# Charger_2023_itr1_ver8.net
KiCad netlist of a schematic drawn in EAGLE
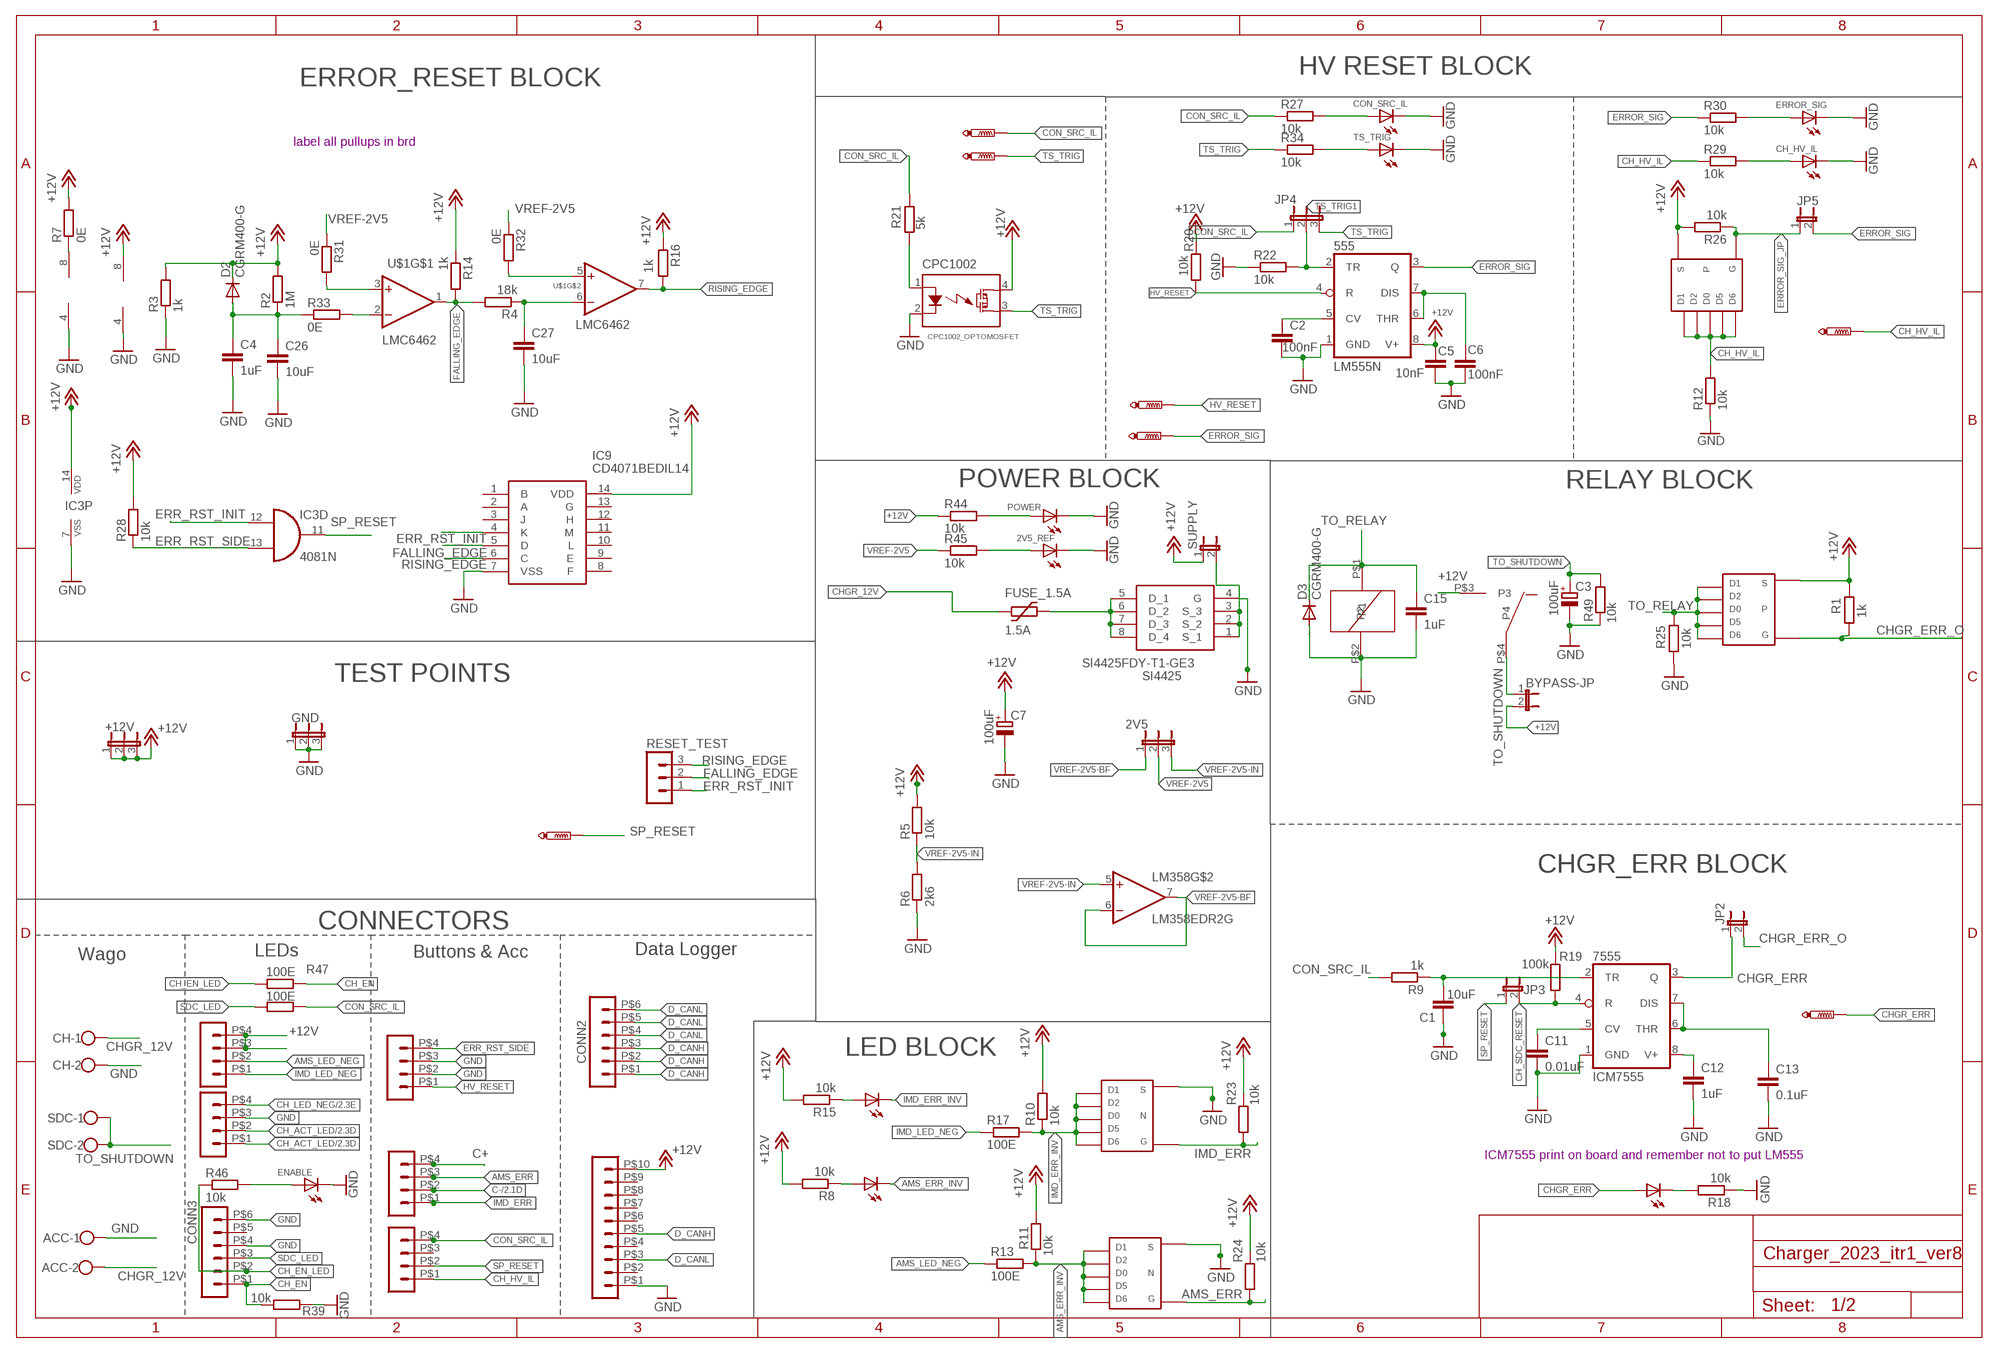
[diagram p0: schematic, sheet 1]
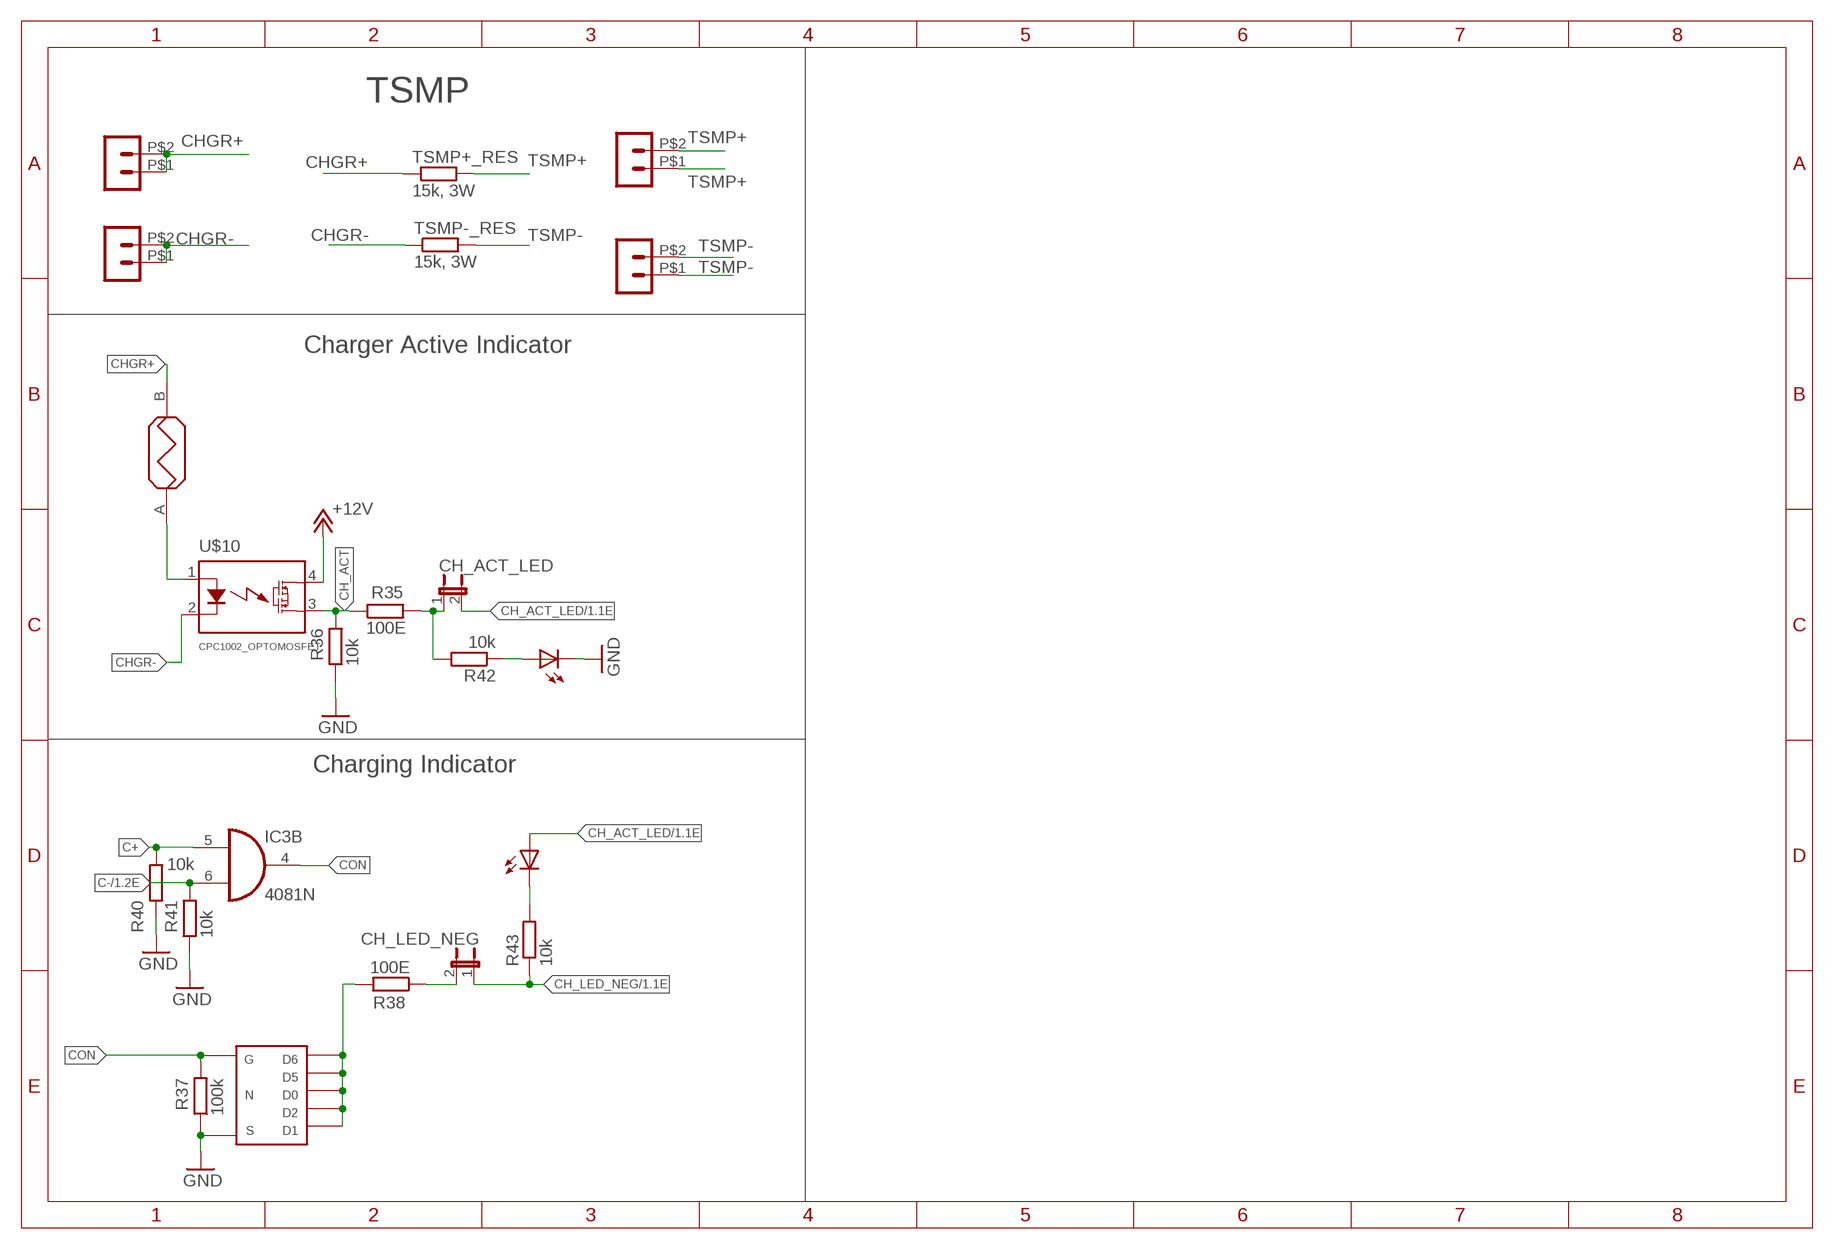
[diagram p1: schematic, sheet 2]

(export (version "E")
  (design (tool "Eeschema 10.0.6"))
  (components
    (comp (ref "+12V")
      (value "JP2E")
      (footprint "eagle-import:JP2")
      (libsource (lib "eagle-import") (part "JP2E"))
    )
    (comp (ref "2V5")
      (value "JP2E")
      (footprint "eagle-import:JP2")
      (libsource (lib "eagle-import") (part "JP2E"))
    )
    (comp (ref "2V5_REF")
      (value "LED-FKIT-1206")
      (footprint "eagle-import:FKIT-LED-1206")
      (libsource (lib "eagle-import") (part "LED-FKIT-1206"))
    )
    (comp (ref "555")
      (value "LM555N")
      (footprint "eagle-import:DIL08")
      (libsource (lib "eagle-import") (part "555NLM"))
    )
    (comp (ref "7555")
      (value "ICM7555")
      (footprint "eagle-import:DIL08")
      (libsource (lib "eagle-import") (part "555NLM"))
    )
    (comp (ref "ACC")
      (value "W237-102")
      (footprint "eagle-import:W237-102")
      (fields (field (name "MPN") "237-102"))
      (libsource (lib "eagle-import") (part "W237-102"))
    )
    (comp (ref "ACU")
      (value "HEADER_POS4_43045-0412")
      (footprint "eagle-import:43045-0412")
      (libsource (lib "eagle-import") (part "HEADER_POS4_?43045-0412"))
    )
    (comp (ref "ACU1")
      (value "HEADER_POS4_43045-0412")
      (footprint "eagle-import:43045-0412")
      (libsource (lib "eagle-import") (part "HEADER_POS4_?43045-0412"))
    )
    (comp (ref "ACU2")
      (value "HEADER_POS4_43045-0412")
      (footprint "eagle-import:43045-0412")
      (libsource (lib "eagle-import") (part "HEADER_POS4_?43045-0412"))
    )
    (comp (ref "ACU3")
      (value "HEADER_POS4_43045-0412")
      (footprint "eagle-import:43045-0412")
      (libsource (lib "eagle-import") (part "HEADER_POS4_?43045-0412"))
    )
    (comp (ref "ACU4")
      (value "HEADER_POS4_43045-0412")
      (footprint "eagle-import:43045-0412")
      (libsource (lib "eagle-import") (part "HEADER_POS4_?43045-0412"))
    )
    (comp (ref "AMS")
      (value "LED-FKIT-1206")
      (footprint "eagle-import:FKIT-LED-1206")
      (libsource (lib "eagle-import") (part "LED-FKIT-1206"))
    )
    (comp (ref "BYPASS-JP")
      (value "JP1E")
      (footprint "eagle-import:JP1")
      (libsource (lib "eagle-import") (part "JP1E"))
    )
    (comp (ref "C1")
      (value "10uF")
      (footprint "eagle-import:C0805")
      (libsource (lib "eagle-import") (part "C-EUC0805"))
    )
    (comp (ref "C2")
      (value "100nF")
      (footprint "eagle-import:C0805")
      (libsource (lib "eagle-import") (part "C-EUC0805"))
    )
    (comp (ref "C3")
      (value "100uF")
      (footprint "eagle-import:E2,5-6")
      (libsource (lib "eagle-import") (part "CPOL-EUE2.5-6"))
    )
    (comp (ref "C4")
      (value "1uF")
      (footprint "eagle-import:C0805")
      (libsource (lib "eagle-import") (part "C-EUC0805"))
    )
    (comp (ref "C5")
      (value "10nF")
      (footprint "eagle-import:C0805")
      (libsource (lib "eagle-import") (part "C-EUC0805"))
    )
    (comp (ref "C6")
      (value "100nF")
      (footprint "eagle-import:C0805")
      (libsource (lib "eagle-import") (part "C-EUC0805"))
    )
    (comp (ref "C7")
      (value "100uF")
      (footprint "eagle-import:E2,5-6")
      (libsource (lib "eagle-import") (part "CPOL-EUE2.5-6"))
    )
    (comp (ref "C11")
      (value "0.01uF")
      (footprint "eagle-import:C0805")
      (libsource (lib "eagle-import") (part "C-EUC0805"))
    )
    (comp (ref "C12")
      (value "1uF")
      (footprint "eagle-import:C0805")
      (libsource (lib "eagle-import") (part "C-EUC0805"))
    )
    (comp (ref "C13")
      (value "0.1uF")
      (footprint "eagle-import:C0805")
      (libsource (lib "eagle-import") (part "C-EUC0805"))
    )
    (comp (ref "C15")
      (value "1uF")
      (footprint "eagle-import:C0805")
      (libsource (lib "eagle-import") (part "C-EUC0805"))
    )
    (comp (ref "C26")
      (value "10uF")
      (footprint "eagle-import:C0805")
      (libsource (lib "eagle-import") (part "C-EUC0805"))
    )
    (comp (ref "C27")
      (value "10uF")
      (footprint "eagle-import:C0805")
      (libsource (lib "eagle-import") (part "C-EUC0805"))
    )
    (comp (ref "CH")
      (value "W237-102")
      (footprint "eagle-import:W237-102")
      (fields (field (name "MPN") "237-102"))
      (libsource (lib "eagle-import") (part "W237-102"))
    )
    (comp (ref "CH-HV-IL")
      (value "PTR1PAD1-13")
      (footprint "eagle-import:P1-13")
      (libsource (lib "eagle-import") (part "PTR1PAD1-13"))
    )
    (comp (ref "CHGR-ERR")
      (value "PTR1PAD1-13")
      (footprint "eagle-import:P1-13")
      (libsource (lib "eagle-import") (part "PTR1PAD1-13"))
    )
    (comp (ref "CHGR_ERR")
      (value "LED-FKIT-1206")
      (footprint "eagle-import:FKIT-LED-1206")
      (libsource (lib "eagle-import") (part "LED-FKIT-1206"))
    )
    (comp (ref "CH_HV_IL")
      (value "LED-FKIT-1206")
      (footprint "eagle-import:FKIT-LED-1206")
      (libsource (lib "eagle-import") (part "LED-FKIT-1206"))
    )
    (comp (ref "CON-SRC-IL")
      (value "PTR1PAD1-13")
      (footprint "eagle-import:P1-13")
      (libsource (lib "eagle-import") (part "PTR1PAD1-13"))
    )
    (comp (ref "CONN2")
      (value "HEADER_POS6_43045-0612")
      (footprint "eagle-import:43045-0612")
      (libsource (lib "eagle-import") (part "HEADER_POS6_?43045-0612"))
    )
    (comp (ref "CONN3")
      (value "HEADER_POS6_43045-0612")
      (footprint "eagle-import:43045-0612")
      (libsource (lib "eagle-import") (part "HEADER_POS6_?43045-0612"))
    )
    (comp (ref "CON_SRC_IL")
      (value "LED-FKIT-1206")
      (footprint "eagle-import:FKIT-LED-1206")
      (libsource (lib "eagle-import") (part "LED-FKIT-1206"))
    )
    (comp (ref "CPC1002")
      (value "CPC1002_OPTOMOSFET")
      (footprint "eagle-import:SOP04")
      (libsource (lib "eagle-import") (part "CPC1002_OPTOMOSFET"))
    )
    (comp (ref "D2")
      (value "CGRM400-G")
      (footprint "eagle-import:SOD-123_MINI-SMA")
      (libsource (lib "eagle-import") (part "CGRM400-G"))
    )
    (comp (ref "D3")
      (value "CGRM400-G")
      (footprint "eagle-import:SOD-123_MINI-SMA")
      (libsource (lib "eagle-import") (part "CGRM400-G"))
    )
    (comp (ref "ENABLE")
      (value "LED-FKIT-1206")
      (footprint "eagle-import:FKIT-LED-1206")
      (libsource (lib "eagle-import") (part "LED-FKIT-1206"))
    )
    (comp (ref "ERROR-SIG")
      (value "PTR1PAD1-13")
      (footprint "eagle-import:P1-13")
      (libsource (lib "eagle-import") (part "PTR1PAD1-13"))
    )
    (comp (ref "ERROR_SIG")
      (value "LED-FKIT-1206")
      (footprint "eagle-import:FKIT-LED-1206")
      (libsource (lib "eagle-import") (part "LED-FKIT-1206"))
    )
    (comp (ref "FUSE_1.5A")
      (value "1.5A")
      (footprint "eagle-import:1206L")
      (fields (field (name "MFR") "Littelfuse"))
      (libsource (lib "eagle-import") (part "1206L"))
    )
    (comp (ref "GND")
      (value "JP2E")
      (footprint "eagle-import:JP2")
      (libsource (lib "eagle-import") (part "JP2E"))
    )
    (comp (ref "HV-RESET")
      (value "PTR1PAD1-13")
      (footprint "eagle-import:P1-13")
      (libsource (lib "eagle-import") (part "PTR1PAD1-13"))
    )
    (comp (ref "IC3")
      (value "4081N")
      (footprint "eagle-import:DIL14")
      (libsource (lib "eagle-import") (part "4081N"))
    )
    (comp (ref "IC9")
      (value "CD4071BEDIL14")
      (footprint "eagle-import:DIL14")
      (libsource (lib "eagle-import") (part "CD4071BEDIL14"))
    )
    (comp (ref "IMD")
      (value "LED-FKIT-1206")
      (footprint "eagle-import:FKIT-LED-1206")
      (libsource (lib "eagle-import") (part "LED-FKIT-1206"))
    )
    (comp (ref "JP2")
      (value "JP1E")
      (footprint "eagle-import:JP1")
      (libsource (lib "eagle-import") (part "JP1E"))
    )
    (comp (ref "JP3")
      (value "JP1E")
      (footprint "eagle-import:JP1")
      (libsource (lib "eagle-import") (part "JP1E"))
    )
    (comp (ref "JP4")
      (value "JP2E")
      (footprint "eagle-import:JP2")
      (libsource (lib "eagle-import") (part "JP2E"))
    )
    (comp (ref "JP5")
      (value "JP1E")
      (footprint "eagle-import:JP1")
      (libsource (lib "eagle-import") (part "JP1E"))
    )
    (comp (ref "LM358")
      (value "LM358EDR2G")
      (footprint "eagle-import:SOIC-8")
      (libsource (lib "eagle-import") (part "LM358EDR2G"))
    )
    (comp (ref "POWER")
      (value "LED-FKIT-1206")
      (footprint "eagle-import:FKIT-LED-1206")
      (libsource (lib "eagle-import") (part "LED-FKIT-1206"))
    )
    (comp (ref "R1")
      (value "1k")
      (footprint "eagle-import:R0805")
      (libsource (lib "eagle-import") (part "R-EU_R0805"))
    )
    (comp (ref "R2")
      (value "1M")
      (footprint "eagle-import:R0805")
      (libsource (lib "eagle-import") (part "R-EU_R0805"))
    )
    (comp (ref "R3")
      (value "1k")
      (footprint "eagle-import:R0805")
      (libsource (lib "eagle-import") (part "R-EU_R0805"))
    )
    (comp (ref "R4")
      (value "18k")
      (footprint "eagle-import:R0805")
      (libsource (lib "eagle-import") (part "R-EU_R0805"))
    )
    (comp (ref "R5")
      (value "10k")
      (footprint "eagle-import:R0805")
      (libsource (lib "eagle-import") (part "R-EU_R0805"))
    )
    (comp (ref "R6")
      (value "2k6")
      (footprint "eagle-import:R0805")
      (libsource (lib "eagle-import") (part "R-EU_R0805"))
    )
    (comp (ref "R7")
      (value "0E")
      (footprint "eagle-import:R0805")
      (libsource (lib "eagle-import") (part "R-EU_R0805"))
    )
    (comp (ref "R8")
      (value "10k")
      (footprint "eagle-import:R0805")
      (libsource (lib "eagle-import") (part "R-EU_R0805"))
    )
    (comp (ref "R9")
      (value "1k")
      (footprint "eagle-import:R0805")
      (libsource (lib "eagle-import") (part "R-EU_R0805"))
    )
    (comp (ref "R10")
      (value "10k")
      (footprint "eagle-import:R0805")
      (libsource (lib "eagle-import") (part "R-EU_R0805"))
    )
    (comp (ref "R11")
      (value "10k")
      (footprint "eagle-import:R0805")
      (libsource (lib "eagle-import") (part "R-EU_R0805"))
    )
    (comp (ref "R12")
      (value "10k")
      (footprint "eagle-import:R0805")
      (libsource (lib "eagle-import") (part "R-EU_R0805"))
    )
    (comp (ref "R13")
      (value "100E")
      (footprint "eagle-import:M0805")
      (libsource (lib "eagle-import") (part "rcl_334_R-EU_M0805"))
    )
    (comp (ref "R14")
      (value "1k")
      (footprint "eagle-import:R0805")
      (libsource (lib "eagle-import") (part "R-EU_R0805"))
    )
    (comp (ref "R15")
      (value "10k")
      (footprint "eagle-import:R0805")
      (libsource (lib "eagle-import") (part "R-EU_R0805"))
    )
    (comp (ref "R16")
      (value "1k")
      (footprint "eagle-import:R0805")
      (libsource (lib "eagle-import") (part "R-EU_R0805"))
    )
    (comp (ref "R17")
      (value "100E")
      (footprint "eagle-import:M0805")
      (libsource (lib "eagle-import") (part "rcl_334_R-EU_M0805"))
    )
    (comp (ref "R18")
      (value "10k")
      (footprint "eagle-import:R0805")
      (libsource (lib "eagle-import") (part "R-EU_R0805"))
    )
    (comp (ref "R19")
      (value "100k")
      (footprint "eagle-import:R0805")
      (libsource (lib "eagle-import") (part "R-EU_R0805"))
    )
    (comp (ref "R20")
      (value "10k")
      (footprint "eagle-import:R0805")
      (libsource (lib "eagle-import") (part "R-EU_R0805"))
    )
    (comp (ref "R21")
      (value "5k")
      (footprint "eagle-import:R0805")
      (libsource (lib "eagle-import") (part "R-EU_R0805"))
    )
    (comp (ref "R22")
      (value "10k")
      (footprint "eagle-import:R0805")
      (libsource (lib "eagle-import") (part "R-EU_R0805"))
    )
    (comp (ref "R23")
      (value "10k")
      (footprint "eagle-import:R0805")
      (libsource (lib "eagle-import") (part "R-EU_R0805"))
    )
    (comp (ref "R24")
      (value "10k")
      (footprint "eagle-import:R0805")
      (libsource (lib "eagle-import") (part "R-EU_R0805"))
    )
    (comp (ref "R25")
      (value "10k")
      (footprint "eagle-import:R0805")
      (libsource (lib "eagle-import") (part "R-EU_R0805"))
    )
    (comp (ref "R26")
      (value "10k")
      (footprint "eagle-import:R0805")
      (libsource (lib "eagle-import") (part "R-EU_R0805"))
    )
    (comp (ref "R27")
      (value "10k")
      (footprint "eagle-import:R0805")
      (libsource (lib "eagle-import") (part "R-EU_R0805"))
    )
    (comp (ref "R28")
      (value "10k")
      (footprint "eagle-import:R0805")
      (libsource (lib "eagle-import") (part "R-EU_R0805"))
    )
    (comp (ref "R29")
      (value "10k")
      (footprint "eagle-import:R0805")
      (libsource (lib "eagle-import") (part "R-EU_R0805"))
    )
    (comp (ref "R30")
      (value "10k")
      (footprint "eagle-import:R0805")
      (libsource (lib "eagle-import") (part "R-EU_R0805"))
    )
    (comp (ref "R31")
      (value "0E")
      (footprint "eagle-import:R0805")
      (libsource (lib "eagle-import") (part "R-EU_R0805"))
    )
    (comp (ref "R32")
      (value "0E")
      (footprint "eagle-import:R0805")
      (libsource (lib "eagle-import") (part "R-EU_R0805"))
    )
    (comp (ref "R33")
      (value "0E")
      (footprint "eagle-import:R0805")
      (libsource (lib "eagle-import") (part "R-EU_R0805"))
    )
    (comp (ref "R34")
      (value "10k")
      (footprint "eagle-import:R0805")
      (libsource (lib "eagle-import") (part "R-EU_R0805"))
    )
    (comp (ref "R39")
      (value "10k")
      (footprint "eagle-import:R0805")
      (libsource (lib "eagle-import") (part "R-EU_R0805"))
    )
    (comp (ref "R44")
      (value "10k")
      (footprint "eagle-import:R0805")
      (libsource (lib "eagle-import") (part "R-EU_R0805"))
    )
    (comp (ref "R45")
      (value "10k")
      (footprint "eagle-import:R0805")
      (libsource (lib "eagle-import") (part "R-EU_R0805"))
    )
    (comp (ref "R46")
      (value "10k")
      (footprint "eagle-import:R0805")
      (libsource (lib "eagle-import") (part "R-EU_R0805"))
    )
    (comp (ref "R47")
      (value "100E")
      (footprint "eagle-import:R0805")
      (libsource (lib "eagle-import") (part "R-EU_R0805"))
    )
    (comp (ref "R48")
      (value "100E")
      (footprint "eagle-import:R0805")
      (libsource (lib "eagle-import") (part "R-EU_R0805"))
    )
    (comp (ref "R49")
      (value "10k")
      (footprint "eagle-import:R0805")
      (libsource (lib "eagle-import") (part "R-EU_R0805"))
    )
    (comp (ref "RESET_TEST")
      (value "MA03-1")
      (footprint "eagle-import:MA03-1")
      (libsource (lib "eagle-import") (part "MA03-1"))
    )
    (comp (ref "SDC")
      (value "W237-102")
      (footprint "eagle-import:W237-102")
      (fields (field (name "MPN") "237-102"))
      (libsource (lib "eagle-import") (part "W237-102"))
    )
    (comp (ref "SI4425")
      (value "SI4425FDY-T1-GE3")
      (footprint "eagle-import:SOIC127P600X175-8N")
      (fields (field (name "MOUSER_PART_NUMBER") "78-SI4425FDY-T1-GE3"))
      (libsource (lib "eagle-import") (part "SI4425FDY-T1-GE3"))
    )
    (comp (ref "SP_RESET")
      (value "PTR1PAD1-13")
      (footprint "eagle-import:P1-13")
      (libsource (lib "eagle-import") (part "PTR1PAD1-13"))
    )
    (comp (ref "SUPPLY")
      (value "JP1E")
      (footprint "eagle-import:JP1")
      (libsource (lib "eagle-import") (part "JP1E"))
    )
    (comp (ref "TS-TRIG")
      (value "PTR1PAD1-13")
      (footprint "eagle-import:P1-13")
      (libsource (lib "eagle-import") (part "PTR1PAD1-13"))
    )
    (comp (ref "TS_TRIG")
      (value "LED-FKIT-1206")
      (footprint "eagle-import:FKIT-LED-1206")
      (libsource (lib "eagle-import") (part "LED-FKIT-1206"))
    )
    (comp (ref "U$1")
      (value "LMC6462")
      (footprint "eagle-import:S08")
      (libsource (lib "eagle-import") (part "LMC6462"))
    )
    (comp (ref "U$3")
      (value "TSOP-6_PMOS")
      (footprint "eagle-import:TSOP-6_PMOS")
      (libsource (lib "eagle-import") (part "TSOP-6_MOS_TSOP-6_PMOS"))
    )
    (comp (ref "U$5")
      (value "TSOP-6_NMOS")
      (footprint "eagle-import:TSOP-6_NMOS")
      (libsource (lib "eagle-import") (part "TSOP-6_NMOS"))
    )
    (comp (ref "U$7")
      (value "TSOP-6_NMOS")
      (footprint "eagle-import:TSOP-6_NMOS")
      (libsource (lib "eagle-import") (part "TSOP-6_NMOS"))
    )
    (comp (ref "U$8")
      (value "TSOP-6_PMOS")
      (footprint "eagle-import:TSOP-6_PMOS")
      (libsource (lib "eagle-import") (part "TSOP-6_PMOS"))
    )
    (comp (ref "U$9")
      (value "G6DN_RELAY")
      (footprint "eagle-import:G6DN_RELAY")
      (libsource (lib "eagle-import") (part "G6DN_RELAY"))
    )
    (comp (ref "X5")
      (value "HEADER_POS10_43045-1012")
      (footprint "eagle-import:43045-1012")
      (libsource (lib "eagle-import") (part "HEADER_POS10_?43045-1012"))
    )
    (comp (ref "CHARGING")
      (value "LED-FKIT-1206")
      (footprint "eagle-import:FKIT-LED-1206")
      (libsource (lib "eagle-import") (part "LED-FKIT-1206"))
    )
    (comp (ref "CH_ACT")
      (value "LED-FKIT-1206")
      (footprint "eagle-import:FKIT-LED-1206")
      (libsource (lib "eagle-import") (part "LED-FKIT-1206"))
    )
    (comp (ref "CH_ACT_LED")
      (value "JP1E")
      (footprint "eagle-import:JP1")
      (libsource (lib "eagle-import") (part "JP1E"))
    )
    (comp (ref "CH_LED_NEG")
      (value "JP1E")
      (footprint "eagle-import:JP1")
      (libsource (lib "eagle-import") (part "JP1E"))
    )
    (comp (ref "LV_ECU")
      (value "HEADER_POS2_43045-0212")
      (footprint "eagle-import:43045-0212")
      (libsource (lib "eagle-import") (part "HEADER_POS2_?43045-0212"))
    )
    (comp (ref "LV_ECU1")
      (value "HEADER_POS2_43045-0212")
      (footprint "eagle-import:43045-0212")
      (libsource (lib "eagle-import") (part "HEADER_POS2_?43045-0212"))
    )
    (comp (ref "LV_ECU2")
      (value "HEADER_POS2_43045-0212")
      (footprint "eagle-import:43045-0212")
      (libsource (lib "eagle-import") (part "HEADER_POS2_?43045-0212"))
    )
    (comp (ref "LV_ECU3")
      (value "HEADER_POS2_43045-0212")
      (footprint "eagle-import:43045-0212")
      (libsource (lib "eagle-import") (part "HEADER_POS2_?43045-0212"))
    )
    (comp (ref "R35")
      (value "100E")
      (footprint "eagle-import:M0805")
      (libsource (lib "eagle-import") (part "rcl_334_R-EU_M0805"))
    )
    (comp (ref "R36")
      (value "10k")
      (footprint "eagle-import:M0805")
      (libsource (lib "eagle-import") (part "rcl_334_R-EU_M0805"))
    )
    (comp (ref "R37")
      (value "100k")
      (footprint "eagle-import:M0805")
      (libsource (lib "eagle-import") (part "rcl_334_R-EU_M0805"))
    )
    (comp (ref "R38")
      (value "100E")
      (footprint "eagle-import:M0805")
      (libsource (lib "eagle-import") (part "rcl_334_R-EU_M0805"))
    )
    (comp (ref "R40")
      (value "10k")
      (footprint "eagle-import:M0805")
      (libsource (lib "eagle-import") (part "rcl_334_R-EU_M0805"))
    )
    (comp (ref "R41")
      (value "10k")
      (footprint "eagle-import:M0805")
      (libsource (lib "eagle-import") (part "rcl_334_R-EU_M0805"))
    )
    (comp (ref "R42")
      (value "10k")
      (footprint "eagle-import:R0805")
      (libsource (lib "eagle-import") (part "R-EU_R0805"))
    )
    (comp (ref "R43")
      (value "10k")
      (footprint "eagle-import:R0805")
      (libsource (lib "eagle-import") (part "R-EU_R0805"))
    )
    (comp (ref "TSMP+_RES")
      (value "15k, 3W")
      (footprint "eagle-import:P0613_15")
      (libsource (lib "eagle-import") (part "rcl_334_R-EU_0613/15"))
    )
    (comp (ref "TSMP-_RES")
      (value "15k, 3W")
      (footprint "eagle-import:P0613_15")
      (libsource (lib "eagle-import") (part "rcl_334_R-EU_0613/15"))
    )
    (comp (ref "U$2_100K10W2")
      (value "POWER_RESISTOR")
      (footprint "eagle-import:POWER_RESISTOR")
      (libsource (lib "eagle-import") (part "POWER_RESISTOR"))
    )
    (comp (ref "U$10")
      (value "CPC1002_OPTOMOSFET")
      (footprint "eagle-import:SOP04")
      (libsource (lib "eagle-import") (part "CPC1002_OPTOMOSFET"))
    )
    (comp (ref "U$12")
      (value "TSOP-6_NMOS")
      (footprint "eagle-import:TSOP-6_NMOS")
      (libsource (lib "eagle-import") (part "TSOP-6_NMOS"))
    )
  )
  (nets
    (net (code "1") (name "+12V") (class "Default")
      (node (ref "+12V") (pin "1") (pinfunction "1_1") (pintype "passive"))
      (node (ref "+12V") (pin "2") (pinfunction "2_2") (pintype "passive"))
      (node (ref "+12V") (pin "3") (pinfunction "3_3") (pintype "passive"))
      (node (ref "555") (pin "8") (pinfunction "V+_8") (pintype "power_in"))
      (node (ref "7555") (pin "8") (pinfunction "V+_8") (pintype "power_in"))
      (node (ref "ACU") (pin "P$3") (pinfunction "3_P$3") (pintype "passive"))
      (node (ref "ACU") (pin "P$4") (pinfunction "4_P$4") (pintype "passive"))
      (node (ref "BYPASS-JP") (pin "2") (pinfunction "2_2") (pintype "passive"))
      (node (ref "C12") (pin "1") (pinfunction "1_1") (pintype "passive"))
      (node (ref "C5") (pin "1") (pinfunction "1_1") (pintype "passive"))
      (node (ref "C7") (pin "+") (pinfunction "+_+") (pintype "passive"))
      (node (ref "CPC1002") (pin "4") (pinfunction "4_4") (pintype "passive"))
      (node (ref "D2") (pin "C") (pinfunction "C_C") (pintype "passive"))
      (node (ref "IC3") (pin "14") (pinfunction "VDD_14") (pintype "power_in"))
      (node (ref "IC9") (pin "14") (pinfunction "VDD_14") (pintype "power_in"))
      (node (ref "LM358") (pin "8") (pinfunction "V+_8") (pintype "power_in"))
      (node (ref "R1") (pin "2") (pinfunction "2_2") (pintype "passive"))
      (node (ref "R10") (pin "2") (pinfunction "2_2") (pintype "passive"))
      (node (ref "R11") (pin "2") (pinfunction "2_2") (pintype "passive"))
      (node (ref "R14") (pin "1") (pinfunction "1_1") (pintype "passive"))
      (node (ref "R15") (pin "2") (pinfunction "2_2") (pintype "passive"))
      (node (ref "R16") (pin "1") (pinfunction "1_1") (pintype "passive"))
      (node (ref "R19") (pin "1") (pinfunction "1_1") (pintype "passive"))
      (node (ref "R2") (pin "2") (pinfunction "2_2") (pintype "passive"))
      (node (ref "R20") (pin "2") (pinfunction "2_2") (pintype "passive"))
      (node (ref "R23") (pin "2") (pinfunction "2_2") (pintype "passive"))
      (node (ref "R24") (pin "2") (pinfunction "2_2") (pintype "passive"))
      (node (ref "R26") (pin "2") (pinfunction "2_2") (pintype "passive"))
      (node (ref "R28") (pin "2") (pinfunction "2_2") (pintype "passive"))
      (node (ref "R3") (pin "2") (pinfunction "2_2") (pintype "passive"))
      (node (ref "R44") (pin "1") (pinfunction "1_1") (pintype "passive"))
      (node (ref "R5") (pin "2") (pinfunction "2_2") (pintype "passive"))
      (node (ref "R7") (pin "2") (pinfunction "2_2") (pintype "passive"))
      (node (ref "R8") (pin "2") (pinfunction "2_2") (pintype "passive"))
      (node (ref "SUPPLY") (pin "1") (pinfunction "1_1") (pintype "passive"))
      (node (ref "U$10") (pin "4") (pinfunction "4_4") (pintype "passive"))
      (node (ref "U$3") (pin "S") (pinfunction "S_S") (pintype "bidirectional"))
      (node (ref "U$8") (pin "S") (pinfunction "S_S") (pintype "bidirectional"))
      (node (ref "U$9") (pin "P$3") (pinfunction "P3_P$3") (pintype "bidirectional"))
      (node (ref "X5") (pin "P$10") (pinfunction "10_P$10") (pintype "passive"))
    )
    (net (code "2") (name "AMS_ERR") (class "Default")
      (node (ref "ACU3") (pin "P$3") (pinfunction "3_P$3") (pintype "passive"))
      (node (ref "R24") (pin "1") (pinfunction "1_1") (pintype "passive"))
      (node (ref "U$5") (pin "G") (pinfunction "G_G") (pintype "bidirectional"))
    )
    (net (code "3") (name "AMS_ERR_INV") (class "Default")
      (node (ref "AMS") (pin "C") (pinfunction "C_C") (pintype "passive"))
      (node (ref "R11") (pin "1") (pinfunction "1_1") (pintype "passive"))
      (node (ref "R13") (pin "2") (pinfunction "2_2") (pintype "passive"))
      (node (ref "U$5") (pin "1") (pinfunction "1_1") (pintype "bidirectional"))
      (node (ref "U$5") (pin "2") (pinfunction "2_2") (pintype "bidirectional"))
      (node (ref "U$5") (pin "5") (pinfunction "5_5") (pintype "bidirectional"))
      (node (ref "U$5") (pin "6") (pinfunction "6_6") (pintype "bidirectional"))
      (node (ref "U$5") (pin "D") (pinfunction "D0_D") (pintype "bidirectional"))
    )
    (net (code "4") (name "AMS_LED_NEG") (class "Default")
      (node (ref "ACU") (pin "P$2") (pinfunction "2_P$2") (pintype "passive"))
      (node (ref "R13") (pin "1") (pinfunction "1_1") (pintype "passive"))
    )
    (net (code "5") (name "C+") (class "Default")
      (node (ref "ACU3") (pin "P$4") (pinfunction "4_P$4") (pintype "passive"))
      (node (ref "IC3") (pin "5") (pinfunction "I0_5") (pintype "input"))
      (node (ref "R40") (pin "2") (pinfunction "2_2") (pintype "passive"))
    )
    (net (code "6") (name "C-") (class "Default")
      (node (ref "ACU3") (pin "P$2") (pinfunction "2_P$2") (pintype "passive"))
      (node (ref "IC3") (pin "6") (pinfunction "I1_6") (pintype "input"))
      (node (ref "R41") (pin "2") (pinfunction "2_2") (pintype "passive"))
    )
    (net (code "7") (name "CHGR+") (class "Default")
      (node (ref "LV_ECU2") (pin "P$1") (pinfunction "1_P$1") (pintype "passive"))
      (node (ref "LV_ECU2") (pin "P$2") (pinfunction "2_P$2") (pintype "passive"))
      (node (ref "TSMP+_RES") (pin "1") (pinfunction "1_1") (pintype "passive"))
      (node (ref "U$2_100K10W2") (pin "B") (pinfunction "B_B") (pintype "bidirectional"))
    )
    (net (code "8") (name "CHGR-") (class "Default")
      (node (ref "LV_ECU3") (pin "P$1") (pinfunction "1_P$1") (pintype "passive"))
      (node (ref "LV_ECU3") (pin "P$2") (pinfunction "2_P$2") (pintype "passive"))
      (node (ref "TSMP-_RES") (pin "1") (pinfunction "1_1") (pintype "passive"))
      (node (ref "U$10") (pin "2") (pinfunction "2_2") (pintype "passive"))
    )
    (net (code "9") (name "CHGR_12V") (class "Default")
      (node (ref "ACC") (pin "2") (pinfunction "KL_2") (pintype "passive"))
      (node (ref "CH") (pin "1") (pinfunction "KL_1") (pintype "passive"))
      (node (ref "FUSE_1.5A") (pin "P$1") (pinfunction "1_P$1") (pintype "passive"))
    )
    (net (code "10") (name "CHGR_ERR") (class "Default")
      (node (ref "7555") (pin "3") (pinfunction "Q_3") (pintype "output"))
      (node (ref "CHGR-ERR") (pin "TP") (pinfunction "TP_TP") (pintype "input"))
      (node (ref "CHGR_ERR") (pin "A") (pinfunction "A_A") (pintype "passive"))
      (node (ref "JP2") (pin "1") (pinfunction "1_1") (pintype "passive"))
    )
    (net (code "11") (name "CHGR_ERR_O") (class "Default")
      (node (ref "JP2") (pin "2") (pinfunction "2_2") (pintype "passive"))
      (node (ref "R1") (pin "1") (pinfunction "1_1") (pintype "passive"))
      (node (ref "U$3") (pin "G") (pinfunction "G_G") (pintype "bidirectional"))
    )
    (net (code "12") (name "CH_ACT") (class "Default")
      (node (ref "R35") (pin "1") (pinfunction "1_1") (pintype "passive"))
      (node (ref "R36") (pin "2") (pinfunction "2_2") (pintype "passive"))
      (node (ref "U$10") (pin "3") (pinfunction "3_3") (pintype "passive"))
    )
    (net (code "13") (name "CH_ACT_LED") (class "Default")
      (node (ref "ACU2") (pin "P$1") (pinfunction "1_P$1") (pintype "passive"))
      (node (ref "ACU2") (pin "P$2") (pinfunction "2_P$2") (pintype "passive"))
      (node (ref "CHARGING") (pin "A") (pinfunction "A_A") (pintype "passive"))
      (node (ref "CH_ACT_LED") (pin "2") (pinfunction "2_2") (pintype "passive"))
    )
    (net (code "14") (name "CH_EN") (class "Default")
      (node (ref "CONN3") (pin "P$1") (pinfunction "1_P$1") (pintype "passive"))
      (node (ref "R39") (pin "2") (pinfunction "2_2") (pintype "passive"))
      (node (ref "R47") (pin "2") (pinfunction "2_2") (pintype "passive"))
    )
    (net (code "15") (name "CH_EN_LED") (class "Default")
      (node (ref "CONN3") (pin "P$2") (pinfunction "2_P$2") (pintype "passive"))
      (node (ref "R46") (pin "1") (pinfunction "1_1") (pintype "passive"))
      (node (ref "R47") (pin "1") (pinfunction "1_1") (pintype "passive"))
    )
    (net (code "16") (name "CH_HV_IL") (class "Default")
      (node (ref "ACU4") (pin "P$1") (pinfunction "1_P$1") (pintype "passive"))
      (node (ref "CH-HV-IL") (pin "TP") (pinfunction "TP_TP") (pintype "input"))
      (node (ref "R12") (pin "2") (pinfunction "2_2") (pintype "passive"))
      (node (ref "R29") (pin "1") (pinfunction "1_1") (pintype "passive"))
      (node (ref "U$8") (pin "1") (pinfunction "1_1") (pintype "bidirectional"))
      (node (ref "U$8") (pin "2") (pinfunction "2_2") (pintype "bidirectional"))
      (node (ref "U$8") (pin "5") (pinfunction "5_5") (pintype "bidirectional"))
      (node (ref "U$8") (pin "6") (pinfunction "6_6") (pintype "bidirectional"))
      (node (ref "U$8") (pin "D") (pinfunction "D0_D") (pintype "bidirectional"))
    )
    (net (code "17") (name "CH_LED_NEG") (class "Default")
      (node (ref "ACU2") (pin "P$4") (pinfunction "4_P$4") (pintype "passive"))
      (node (ref "CH_LED_NEG") (pin "1") (pinfunction "1_1") (pintype "passive"))
      (node (ref "R43") (pin "1") (pinfunction "1_1") (pintype "passive"))
    )
    (net (code "18") (name "CH_SDC_RESET") (class "Default")
      (node (ref "7555") (pin "4") (pinfunction "R_4") (pintype "input"))
      (node (ref "JP3") (pin "2") (pinfunction "2_2") (pintype "passive"))
      (node (ref "R19") (pin "2") (pinfunction "2_2") (pintype "passive"))
    )
    (net (code "19") (name "CON") (class "Default")
      (node (ref "IC3") (pin "4") (pinfunction "O_4") (pintype "output"))
      (node (ref "R37") (pin "2") (pinfunction "2_2") (pintype "passive"))
      (node (ref "U$12") (pin "G") (pinfunction "G_G") (pintype "bidirectional"))
    )
    (net (code "20") (name "CON_SRC_IL") (class "Default")
      (node (ref "ACU4") (pin "P$4") (pinfunction "4_P$4") (pintype "passive"))
      (node (ref "CON-SRC-IL") (pin "TP") (pinfunction "TP_TP") (pintype "input"))
      (node (ref "JP4") (pin "1") (pinfunction "1_1") (pintype "passive"))
      (node (ref "R21") (pin "2") (pinfunction "2_2") (pintype "passive"))
      (node (ref "R27") (pin "1") (pinfunction "1_1") (pintype "passive"))
      (node (ref "R48") (pin "2") (pinfunction "2_2") (pintype "passive"))
      (node (ref "R9") (pin "2") (pinfunction "2_2") (pintype "passive"))
    )
    (net (code "21") (name "D_CANH") (class "Default")
      (node (ref "CONN2") (pin "P$1") (pinfunction "1_P$1") (pintype "passive"))
      (node (ref "CONN2") (pin "P$2") (pinfunction "2_P$2") (pintype "passive"))
      (node (ref "CONN2") (pin "P$3") (pinfunction "3_P$3") (pintype "passive"))
      (node (ref "X5") (pin "P$5") (pinfunction "5_P$5") (pintype "passive"))
    )
    (net (code "22") (name "D_CANL") (class "Default")
      (node (ref "CONN2") (pin "P$4") (pinfunction "4_P$4") (pintype "passive"))
      (node (ref "CONN2") (pin "P$5") (pinfunction "5_P$5") (pintype "passive"))
      (node (ref "CONN2") (pin "P$6") (pinfunction "6_P$6") (pintype "passive"))
      (node (ref "X5") (pin "P$3") (pinfunction "3_P$3") (pintype "passive"))
    )
    (net (code "23") (name "ERROR_SIG") (class "Default")
      (node (ref "555") (pin "3") (pinfunction "Q_3") (pintype "output"))
      (node (ref "ERROR-SIG") (pin "TP") (pinfunction "TP_TP") (pintype "input"))
      (node (ref "JP5") (pin "2") (pinfunction "2_2") (pintype "passive"))
      (node (ref "R30") (pin "1") (pinfunction "1_1") (pintype "passive"))
    )
    (net (code "24") (name "ERROR_SIG_JP") (class "Default")
      (node (ref "JP5") (pin "1") (pinfunction "1_1") (pintype "passive"))
      (node (ref "R26") (pin "1") (pinfunction "1_1") (pintype "passive"))
      (node (ref "U$8") (pin "G") (pinfunction "G_G") (pintype "bidirectional"))
    )
    (net (code "25") (name "ERR_RST_INIT") (class "Default")
      (node (ref "IC3") (pin "12") (pinfunction "I0_12") (pintype "input"))
      (node (ref "IC9") (pin "4") (pinfunction "K_4") (pintype "bidirectional"))
      (node (ref "RESET_TEST") (pin "1") (pinfunction "1_1") (pintype "passive"))
    )
    (net (code "26") (name "ERR_RST_SIDE") (class "Default")
      (node (ref "ACU1") (pin "P$4") (pinfunction "4_P$4") (pintype "passive"))
      (node (ref "IC3") (pin "13") (pinfunction "I1_13") (pintype "input"))
      (node (ref "R28") (pin "1") (pinfunction "1_1") (pintype "passive"))
    )
    (net (code "27") (name "FALLING_EDGE") (class "Default")
      (node (ref "IC9") (pin "5") (pinfunction "D_5") (pintype "bidirectional"))
      (node (ref "R14") (pin "2") (pinfunction "2_2") (pintype "passive"))
      (node (ref "R4") (pin "2") (pinfunction "2_2") (pintype "passive"))
      (node (ref "RESET_TEST") (pin "2") (pinfunction "2_2") (pintype "passive"))
      (node (ref "U$1") (pin "1") (pinfunction "OUT_1") (pintype "output"))
    )
    (net (code "28") (name "GND") (class "Default")
      (node (ref "2V5_REF") (pin "C") (pinfunction "C_C") (pintype "passive"))
      (node (ref "555") (pin "1") (pinfunction "GND_1") (pintype "power_in"))
      (node (ref "7555") (pin "1") (pinfunction "GND_1") (pintype "power_in"))
      (node (ref "ACC") (pin "1") (pinfunction "KL_1") (pintype "passive"))
      (node (ref "ACU1") (pin "P$2") (pinfunction "2_P$2") (pintype "passive"))
      (node (ref "ACU1") (pin "P$3") (pinfunction "3_P$3") (pintype "passive"))
      (node (ref "ACU2") (pin "P$3") (pinfunction "3_P$3") (pintype "passive"))
      (node (ref "C1") (pin "1") (pinfunction "1_1") (pintype "passive"))
      (node (ref "C11") (pin "2") (pinfunction "2_2") (pintype "passive"))
      (node (ref "C12") (pin "2") (pinfunction "2_2") (pintype "passive"))
      (node (ref "C13") (pin "2") (pinfunction "2_2") (pintype "passive"))
      (node (ref "C15") (pin "2") (pinfunction "2_2") (pintype "passive"))
      (node (ref "C2") (pin "2") (pinfunction "2_2") (pintype "passive"))
      (node (ref "C26") (pin "2") (pinfunction "2_2") (pintype "passive"))
      (node (ref "C27") (pin "2") (pinfunction "2_2") (pintype "passive"))
      (node (ref "C3") (pin "-") (pinfunction "-_-") (pintype "passive"))
      (node (ref "C4") (pin "2") (pinfunction "2_2") (pintype "passive"))
      (node (ref "C5") (pin "2") (pinfunction "2_2") (pintype "passive"))
      (node (ref "C6") (pin "2") (pinfunction "2_2") (pintype "passive"))
      (node (ref "C7") (pin "-") (pinfunction "-_-") (pintype "passive"))
      (node (ref "CH") (pin "2") (pinfunction "KL_2") (pintype "passive"))
      (node (ref "CH_ACT") (pin "C") (pinfunction "C_C") (pintype "passive"))
      (node (ref "CH_HV_IL") (pin "C") (pinfunction "C_C") (pintype "passive"))
      (node (ref "CONN3") (pin "P$4") (pinfunction "4_P$4") (pintype "passive"))
      (node (ref "CONN3") (pin "P$6") (pinfunction "6_P$6") (pintype "passive"))
      (node (ref "CON_SRC_IL") (pin "C") (pinfunction "C_C") (pintype "passive"))
      (node (ref "CPC1002") (pin "2") (pinfunction "2_2") (pintype "passive"))
      (node (ref "D3") (pin "A") (pinfunction "A_A") (pintype "passive"))
      (node (ref "ENABLE") (pin "C") (pinfunction "C_C") (pintype "passive"))
      (node (ref "ERROR_SIG") (pin "C") (pinfunction "C_C") (pintype "passive"))
      (node (ref "GND") (pin "1") (pinfunction "1_1") (pintype "passive"))
      (node (ref "GND") (pin "2") (pinfunction "2_2") (pintype "passive"))
      (node (ref "GND") (pin "3") (pinfunction "3_3") (pintype "passive"))
      (node (ref "IC3") (pin "7") (pinfunction "VSS_7") (pintype "power_in"))
      (node (ref "IC9") (pin "7") (pinfunction "VSS_7") (pintype "power_in"))
      (node (ref "LM358") (pin "4") (pinfunction "V-_4") (pintype "power_in"))
      (node (ref "POWER") (pin "C") (pinfunction "C_C") (pintype "passive"))
      (node (ref "R12") (pin "1") (pinfunction "1_1") (pintype "passive"))
      (node (ref "R18") (pin "1") (pinfunction "1_1") (pintype "passive"))
      (node (ref "R22") (pin "1") (pinfunction "1_1") (pintype "passive"))
      (node (ref "R25") (pin "1") (pinfunction "1_1") (pintype "passive"))
      (node (ref "R3") (pin "1") (pinfunction "1_1") (pintype "passive"))
      (node (ref "R36") (pin "1") (pinfunction "1_1") (pintype "passive"))
      (node (ref "R37") (pin "1") (pinfunction "1_1") (pintype "passive"))
      (node (ref "R39") (pin "1") (pinfunction "1_1") (pintype "passive"))
      (node (ref "R40") (pin "1") (pinfunction "1_1") (pintype "passive"))
      (node (ref "R41") (pin "1") (pinfunction "1_1") (pintype "passive"))
      (node (ref "R49") (pin "1") (pinfunction "1_1") (pintype "passive"))
      (node (ref "R6") (pin "1") (pinfunction "1_1") (pintype "passive"))
      (node (ref "SI4425") (pin "4") (pinfunction "G_4") (pintype "bidirectional"))
      (node (ref "TS_TRIG") (pin "C") (pinfunction "C_C") (pintype "passive"))
      (node (ref "U$1") (pin "4") (pinfunction "V-_4") (pintype "power_in"))
      (node (ref "U$12") (pin "S") (pinfunction "S_S") (pintype "bidirectional"))
      (node (ref "U$5") (pin "S") (pinfunction "S_S") (pintype "bidirectional"))
      (node (ref "U$7") (pin "S") (pinfunction "S_S") (pintype "bidirectional"))
      (node (ref "U$9") (pin "P$2") (pinfunction "P2_P$2") (pintype "bidirectional"))
      (node (ref "X5") (pin "P$1") (pinfunction "1_P$1") (pintype "passive"))
    )
    (net (code "29") (name "HV_RESET") (class "Default")
      (node (ref "555") (pin "4") (pinfunction "R_4") (pintype "input"))
      (node (ref "ACU1") (pin "P$1") (pinfunction "1_P$1") (pintype "passive"))
      (node (ref "HV-RESET") (pin "TP") (pinfunction "TP_TP") (pintype "input"))
      (node (ref "R20") (pin "1") (pinfunction "1_1") (pintype "passive"))
    )
    (net (code "30") (name "IMD_ERR") (class "Default")
      (node (ref "ACU3") (pin "P$1") (pinfunction "1_P$1") (pintype "passive"))
      (node (ref "R23") (pin "1") (pinfunction "1_1") (pintype "passive"))
      (node (ref "U$7") (pin "G") (pinfunction "G_G") (pintype "bidirectional"))
    )
    (net (code "31") (name "IMD_ERR_INV") (class "Default")
      (node (ref "IMD") (pin "C") (pinfunction "C_C") (pintype "passive"))
      (node (ref "R10") (pin "1") (pinfunction "1_1") (pintype "passive"))
      (node (ref "R17") (pin "2") (pinfunction "2_2") (pintype "passive"))
      (node (ref "U$7") (pin "1") (pinfunction "1_1") (pintype "bidirectional"))
      (node (ref "U$7") (pin "2") (pinfunction "2_2") (pintype "bidirectional"))
      (node (ref "U$7") (pin "5") (pinfunction "5_5") (pintype "bidirectional"))
      (node (ref "U$7") (pin "6") (pinfunction "6_6") (pintype "bidirectional"))
      (node (ref "U$7") (pin "D") (pinfunction "D0_D") (pintype "bidirectional"))
    )
    (net (code "32") (name "IMD_LED_NEG") (class "Default")
      (node (ref "ACU") (pin "P$1") (pinfunction "1_P$1") (pintype "passive"))
      (node (ref "R17") (pin "1") (pinfunction "1_1") (pintype "passive"))
    )
    (net (code "33") (name "Net-(2V5_REF-PadA)") (class "Default")
      (node (ref "2V5_REF") (pin "A") (pinfunction "A_A") (pintype "passive"))
      (node (ref "R45") (pin "2") (pinfunction "2_2") (pintype "passive"))
    )
    (net (code "34") (name "Net-(555-CV)") (class "Default")
      (node (ref "555") (pin "5") (pinfunction "CV_5") (pintype "input"))
      (node (ref "C2") (pin "1") (pinfunction "1_1") (pintype "passive"))
    )
    (net (code "35") (name "Net-(555-DIS)") (class "Default")
      (node (ref "555") (pin "6") (pinfunction "THR_6") (pintype "input"))
      (node (ref "555") (pin "7") (pinfunction "DIS_7") (pintype "input"))
      (node (ref "C6") (pin "1") (pinfunction "1_1") (pintype "passive"))
    )
    (net (code "36") (name "Net-(7555-CV)") (class "Default")
      (node (ref "7555") (pin "5") (pinfunction "CV_5") (pintype "input"))
      (node (ref "C11") (pin "1") (pinfunction "1_1") (pintype "passive"))
    )
    (net (code "37") (name "Net-(7555-DIS)") (class "Default")
      (node (ref "7555") (pin "6") (pinfunction "THR_6") (pintype "input"))
      (node (ref "7555") (pin "7") (pinfunction "DIS_7") (pintype "input"))
      (node (ref "C13") (pin "1") (pinfunction "1_1") (pintype "passive"))
    )
    (net (code "38") (name "Net-(7555-TR)") (class "Default")
      (node (ref "7555") (pin "2") (pinfunction "TR_2") (pintype "input"))
      (node (ref "C1") (pin "2") (pinfunction "2_2") (pintype "passive"))
      (node (ref "R9") (pin "1") (pinfunction "1_1") (pintype "passive"))
    )
    (net (code "39") (name "Net-(AMS-PadA)") (class "Default")
      (node (ref "AMS") (pin "A") (pinfunction "A_A") (pintype "passive"))
      (node (ref "R8") (pin "1") (pinfunction "1_1") (pintype "passive"))
    )
    (net (code "40") (name "Net-(C26-Pad1)") (class "Default")
      (node (ref "C26") (pin "1") (pinfunction "1_1") (pintype "passive"))
      (node (ref "C4") (pin "1") (pinfunction "1_1") (pintype "passive"))
      (node (ref "D2") (pin "A") (pinfunction "A_A") (pintype "passive"))
      (node (ref "R2") (pin "1") (pinfunction "1_1") (pintype "passive"))
      (node (ref "R33") (pin "1") (pinfunction "1_1") (pintype "passive"))
    )
    (net (code "41") (name "Net-(CHARGING-PadC)") (class "Default")
      (node (ref "CHARGING") (pin "C") (pinfunction "C_C") (pintype "passive"))
      (node (ref "R43") (pin "2") (pinfunction "2_2") (pintype "passive"))
    )
    (net (code "42") (name "Net-(CHGR_ERR-PadC)") (class "Default")
      (node (ref "CHGR_ERR") (pin "C") (pinfunction "C_C") (pintype "passive"))
      (node (ref "R18") (pin "2") (pinfunction "2_2") (pintype "passive"))
    )
    (net (code "43") (name "Net-(CH_ACT-PadA)") (class "Default")
      (node (ref "CH_ACT") (pin "A") (pinfunction "A_A") (pintype "passive"))
      (node (ref "R42") (pin "1") (pinfunction "1_1") (pintype "passive"))
    )
    (net (code "44") (name "Net-(CH_ACT_LED-Pad1)") (class "Default")
      (node (ref "CH_ACT_LED") (pin "1") (pinfunction "1_1") (pintype "passive"))
      (node (ref "R35") (pin "2") (pinfunction "2_2") (pintype "passive"))
      (node (ref "R42") (pin "2") (pinfunction "2_2") (pintype "passive"))
    )
    (net (code "45") (name "Net-(CH_HV_IL-PadA)") (class "Default")
      (node (ref "CH_HV_IL") (pin "A") (pinfunction "A_A") (pintype "passive"))
      (node (ref "R29") (pin "2") (pinfunction "2_2") (pintype "passive"))
    )
    (net (code "46") (name "Net-(CH_LED_NEG-Pad2)") (class "Default")
      (node (ref "CH_LED_NEG") (pin "2") (pinfunction "2_2") (pintype "passive"))
      (node (ref "R38") (pin "1") (pinfunction "1_1") (pintype "passive"))
    )
    (net (code "47") (name "Net-(CON_SRC_IL-PadA)") (class "Default")
      (node (ref "CON_SRC_IL") (pin "A") (pinfunction "A_A") (pintype "passive"))
      (node (ref "R27") (pin "2") (pinfunction "2_2") (pintype "passive"))
    )
    (net (code "48") (name "Net-(CPC1002-Pad1)") (class "Default")
      (node (ref "CPC1002") (pin "1") (pinfunction "1_1") (pintype "passive"))
      (node (ref "R21") (pin "1") (pinfunction "1_1") (pintype "passive"))
    )
    (net (code "49") (name "Net-(ENABLE-PadA)") (class "Default")
      (node (ref "ENABLE") (pin "A") (pinfunction "A_A") (pintype "passive"))
      (node (ref "R46") (pin "2") (pinfunction "2_2") (pintype "passive"))
    )
    (net (code "50") (name "Net-(ERROR_SIG-PadA)") (class "Default")
      (node (ref "ERROR_SIG") (pin "A") (pinfunction "A_A") (pintype "passive"))
      (node (ref "R30") (pin "2") (pinfunction "2_2") (pintype "passive"))
    )
    (net (code "51") (name "Net-(FUSE_1.5A-2)") (class "Default")
      (node (ref "FUSE_1.5A") (pin "P$2") (pinfunction "2_P$2") (pintype "passive"))
      (node (ref "SI4425") (pin "5") (pinfunction "D_1_5") (pintype "bidirectional"))
      (node (ref "SI4425") (pin "6") (pinfunction "D_2_6") (pintype "bidirectional"))
      (node (ref "SI4425") (pin "7") (pinfunction "D_3_7") (pintype "bidirectional"))
      (node (ref "SI4425") (pin "8") (pinfunction "D_4_8") (pintype "bidirectional"))
    )
    (net (code "52") (name "Net-(IMD-PadA)") (class "Default")
      (node (ref "IMD") (pin "A") (pinfunction "A_A") (pintype "passive"))
      (node (ref "R15") (pin "1") (pinfunction "1_1") (pintype "passive"))
    )
    (net (code "53") (name "Net-(POWER-PadA)") (class "Default")
      (node (ref "POWER") (pin "A") (pinfunction "A_A") (pintype "passive"))
      (node (ref "R44") (pin "2") (pinfunction "2_2") (pintype "passive"))
    )
    (net (code "54") (name "Net-(R34-Pad2)") (class "Default")
      (node (ref "R34") (pin "2") (pinfunction "2_2") (pintype "passive"))
      (node (ref "TS_TRIG") (pin "A") (pinfunction "A_A") (pintype "passive"))
    )
    (net (code "55") (name "Net-(SI4425-S_1)") (class "Default")
      (node (ref "SI4425") (pin "1") (pinfunction "S_1_1") (pintype "bidirectional"))
      (node (ref "SI4425") (pin "2") (pinfunction "S_2_2") (pintype "bidirectional"))
      (node (ref "SI4425") (pin "3") (pinfunction "S_3_3") (pintype "bidirectional"))
      (node (ref "SUPPLY") (pin "2") (pinfunction "2_2") (pintype "passive"))
    )
    (net (code "56") (name "Net-(U$1A-+IN)") (class "Default")
      (node (ref "R31") (pin "2") (pinfunction "2_2") (pintype "passive"))
      (node (ref "U$1") (pin "3") (pinfunction "+IN_3") (pintype "input"))
    )
    (net (code "57") (name "Net-(U$1A--IN)") (class "Default")
      (node (ref "R33") (pin "2") (pinfunction "2_2") (pintype "passive"))
      (node (ref "U$1") (pin "2") (pinfunction "-IN_2") (pintype "input"))
    )
    (net (code "58") (name "Net-(U$1B-+IN)") (class "Default")
      (node (ref "R32") (pin "2") (pinfunction "2_2") (pintype "passive"))
      (node (ref "U$1") (pin "5") (pinfunction "+IN_5") (pintype "input"))
    )
    (net (code "59") (name "Net-(U$1B--IN)") (class "Default")
      (node (ref "C27") (pin "1") (pinfunction "1_1") (pintype "passive"))
      (node (ref "R4") (pin "1") (pinfunction "1_1") (pintype "passive"))
      (node (ref "U$1") (pin "6") (pinfunction "-IN_6") (pintype "input"))
    )
    (net (code "60") (name "Net-(U$1C-V+)") (class "Default")
      (node (ref "R7") (pin "1") (pinfunction "1_1") (pintype "passive"))
      (node (ref "U$1") (pin "8") (pinfunction "V+_8") (pintype "power_in"))
    )
    (net (code "61") (name "Net-(U$10-Pad1)") (class "Default")
      (node (ref "U$10") (pin "1") (pinfunction "1_1") (pintype "passive"))
      (node (ref "U$2_100K10W2") (pin "A") (pinfunction "A_A") (pintype "bidirectional"))
    )
    (net (code "62") (name "Net-(U$12-D0)") (class "Default")
      (node (ref "R38") (pin "2") (pinfunction "2_2") (pintype "passive"))
      (node (ref "U$12") (pin "1") (pinfunction "1_1") (pintype "bidirectional"))
      (node (ref "U$12") (pin "2") (pinfunction "2_2") (pintype "bidirectional"))
      (node (ref "U$12") (pin "5") (pinfunction "5_5") (pintype "bidirectional"))
      (node (ref "U$12") (pin "6") (pinfunction "6_6") (pintype "bidirectional"))
      (node (ref "U$12") (pin "D") (pinfunction "D0_D") (pintype "bidirectional"))
    )
    (net (code "63") (name "RISING_EDGE") (class "Default")
      (node (ref "IC9") (pin "6") (pinfunction "C_6") (pintype "bidirectional"))
      (node (ref "R16") (pin "2") (pinfunction "2_2") (pintype "passive"))
      (node (ref "RESET_TEST") (pin "3") (pinfunction "3_3") (pintype "passive"))
      (node (ref "U$1") (pin "7") (pinfunction "OUT_7") (pintype "output"))
    )
    (net (code "64") (name "SDC_LED") (class "Default")
      (node (ref "CONN3") (pin "P$3") (pinfunction "3_P$3") (pintype "passive"))
      (node (ref "R48") (pin "1") (pinfunction "1_1") (pintype "passive"))
    )
    (net (code "65") (name "SP_RESET") (class "Default")
      (node (ref "ACU4") (pin "P$2") (pinfunction "2_P$2") (pintype "passive"))
      (node (ref "IC3") (pin "11") (pinfunction "O_11") (pintype "output"))
      (node (ref "JP3") (pin "1") (pinfunction "1_1") (pintype "passive"))
      (node (ref "SP_RESET") (pin "TP") (pinfunction "TP_TP") (pintype "input"))
    )
    (net (code "66") (name "TO_RELAY") (class "Default")
      (node (ref "C15") (pin "1") (pinfunction "1_1") (pintype "passive"))
      (node (ref "D3") (pin "C") (pinfunction "C_C") (pintype "passive"))
      (node (ref "R25") (pin "2") (pinfunction "2_2") (pintype "passive"))
      (node (ref "U$3") (pin "1") (pinfunction "1_1") (pintype "bidirectional"))
      (node (ref "U$3") (pin "2") (pinfunction "2_2") (pintype "bidirectional"))
      (node (ref "U$3") (pin "5") (pinfunction "5_5") (pintype "bidirectional"))
      (node (ref "U$3") (pin "6") (pinfunction "6_6") (pintype "bidirectional"))
      (node (ref "U$3") (pin "D") (pinfunction "D0_D") (pintype "bidirectional"))
      (node (ref "U$9") (pin "P$1") (pinfunction "P1_P$1") (pintype "bidirectional"))
    )
    (net (code "67") (name "TO_SHUTDOWN") (class "Default")
      (node (ref "BYPASS-JP") (pin "1") (pinfunction "1_1") (pintype "passive"))
      (node (ref "C3") (pin "+") (pinfunction "+_+") (pintype "passive"))
      (node (ref "R49") (pin "2") (pinfunction "2_2") (pintype "passive"))
      (node (ref "SDC") (pin "1") (pinfunction "KL_1") (pintype "passive"))
      (node (ref "SDC") (pin "2") (pinfunction "KL_2") (pintype "passive"))
      (node (ref "U$9") (pin "P$4") (pinfunction "P4_P$4") (pintype "bidirectional"))
    )
    (net (code "68") (name "TSMP+") (class "Default")
      (node (ref "LV_ECU") (pin "P$1") (pinfunction "1_P$1") (pintype "passive"))
      (node (ref "LV_ECU") (pin "P$2") (pinfunction "2_P$2") (pintype "passive"))
      (node (ref "TSMP+_RES") (pin "2") (pinfunction "2_2") (pintype "passive"))
    )
    (net (code "69") (name "TSMP-") (class "Default")
      (node (ref "LV_ECU1") (pin "P$1") (pinfunction "1_P$1") (pintype "passive"))
      (node (ref "LV_ECU1") (pin "P$2") (pinfunction "2_P$2") (pintype "passive"))
      (node (ref "TSMP-_RES") (pin "2") (pinfunction "2_2") (pintype "passive"))
    )
    (net (code "70") (name "TS_TRIG") (class "Default")
      (node (ref "CPC1002") (pin "3") (pinfunction "3_3") (pintype "passive"))
      (node (ref "JP4") (pin "3") (pinfunction "3_3") (pintype "passive"))
      (node (ref "R34") (pin "1") (pinfunction "1_1") (pintype "passive"))
      (node (ref "TS-TRIG") (pin "TP") (pinfunction "TP_TP") (pintype "input"))
    )
    (net (code "71") (name "TS_TRIG1") (class "Default")
      (node (ref "555") (pin "2") (pinfunction "TR_2") (pintype "input"))
      (node (ref "JP4") (pin "2") (pinfunction "2_2") (pintype "passive"))
      (node (ref "R22") (pin "2") (pinfunction "2_2") (pintype "passive"))
    )
    (net (code "72") (name "VREF-2V5") (class "Default")
      (node (ref "2V5") (pin "2") (pinfunction "2_2") (pintype "passive"))
      (node (ref "R31") (pin "1") (pinfunction "1_1") (pintype "passive"))
      (node (ref "R32") (pin "1") (pinfunction "1_1") (pintype "passive"))
      (node (ref "R45") (pin "1") (pinfunction "1_1") (pintype "passive"))
    )
    (net (code "73") (name "VREF-2V5-BF") (class "Default")
      (node (ref "2V5") (pin "1") (pinfunction "1_1") (pintype "passive"))
      (node (ref "LM358") (pin "6") (pinfunction "-IN_6") (pintype "input"))
      (node (ref "LM358") (pin "7") (pinfunction "OUT_7") (pintype "output"))
    )
    (net (code "74") (name "VREF-2V5-IN") (class "Default")
      (node (ref "2V5") (pin "3") (pinfunction "3_3") (pintype "passive"))
      (node (ref "LM358") (pin "5") (pinfunction "+IN_5") (pintype "input"))
      (node (ref "R5") (pin "1") (pinfunction "1_1") (pintype "passive"))
      (node (ref "R6") (pin "2") (pinfunction "2_2") (pintype "passive"))
    )
    (net (code "75") (name "unconnected-(ACU4-3-PadP$3)") (class "Default")
      (node (ref "ACU4") (pin "P$3") (pinfunction "3_P$3") (pintype "passive"))
    )
    (net (code "76") (name "unconnected-(CONN3-5-PadP$5)") (class "Default")
      (node (ref "CONN3") (pin "P$5") (pinfunction "5_P$5") (pintype "passive"))
    )
    (net (code "77") (name "unconnected-(IC9-A-Pad2)") (class "Default")
      (node (ref "IC9") (pin "2") (pinfunction "A_2") (pintype "bidirectional"))
    )
    (net (code "78") (name "unconnected-(IC9-B-Pad1)") (class "Default")
      (node (ref "IC9") (pin "1") (pinfunction "B_1") (pintype "bidirectional"))
    )
    (net (code "79") (name "unconnected-(IC9-E-Pad9)") (class "Default")
      (node (ref "IC9") (pin "9") (pinfunction "E_9") (pintype "bidirectional"))
    )
    (net (code "80") (name "unconnected-(IC9-F-Pad8)") (class "Default")
      (node (ref "IC9") (pin "8") (pinfunction "F_8") (pintype "bidirectional"))
    )
    (net (code "81") (name "unconnected-(IC9-G-Pad13)") (class "Default")
      (node (ref "IC9") (pin "13") (pinfunction "G_13") (pintype "bidirectional"))
    )
    (net (code "82") (name "unconnected-(IC9-H-Pad12)") (class "Default")
      (node (ref "IC9") (pin "12") (pinfunction "H_12") (pintype "bidirectional"))
    )
    (net (code "83") (name "unconnected-(IC9-J-Pad3)") (class "Default")
      (node (ref "IC9") (pin "3") (pinfunction "J_3") (pintype "bidirectional"))
    )
    (net (code "84") (name "unconnected-(IC9-L-Pad10)") (class "Default")
      (node (ref "IC9") (pin "10") (pinfunction "L_10") (pintype "bidirectional"))
    )
    (net (code "85") (name "unconnected-(IC9-M-Pad11)") (class "Default")
      (node (ref "IC9") (pin "11") (pinfunction "M_11") (pintype "bidirectional"))
    )
    (net (code "86") (name "unconnected-(X5-2-PadP$2)") (class "Default")
      (node (ref "X5") (pin "P$2") (pinfunction "2_P$2") (pintype "passive"))
    )
    (net (code "87") (name "unconnected-(X5-4-PadP$4)") (class "Default")
      (node (ref "X5") (pin "P$4") (pinfunction "4_P$4") (pintype "passive"))
    )
    (net (code "88") (name "unconnected-(X5-6-PadP$6)") (class "Default")
      (node (ref "X5") (pin "P$6") (pinfunction "6_P$6") (pintype "passive"))
    )
    (net (code "89") (name "unconnected-(X5-7-PadP$7)") (class "Default")
      (node (ref "X5") (pin "P$7") (pinfunction "7_P$7") (pintype "passive"))
    )
    (net (code "90") (name "unconnected-(X5-8-PadP$8)") (class "Default")
      (node (ref "X5") (pin "P$8") (pinfunction "8_P$8") (pintype "passive"))
    )
    (net (code "91") (name "unconnected-(X5-9-PadP$9)") (class "Default")
      (node (ref "X5") (pin "P$9") (pinfunction "9_P$9") (pintype "passive"))
    )
  )
)
